# Kippstufe_astabil.net
KiCad netlist of a schematic drawn in EAGLE
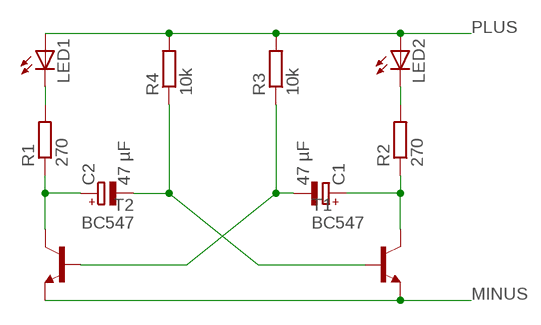
[diagram p0: schematic, sheet 1]

(export (version "E")
  (design (tool "Eeschema 10.0.6"))
  (components
    (comp (ref "C1")
      (value "47 µF")
      (footprint "eagle-import:B45181B")
      (libsource (lib "eagle-import") (part "CPOL-EUB45181B"))
    )
    (comp (ref "C2")
      (value "47 µF")
      (footprint "eagle-import:B45181B")
      (libsource (lib "eagle-import") (part "CPOL-EUB45181B"))
    )
    (comp (ref "LED1")
      (value "LED5MM")
      (footprint "eagle-import:LED5MM")
      (libsource (lib "eagle-import") (part "LED5MM"))
    )
    (comp (ref "LED2")
      (value "LED5MM")
      (footprint "eagle-import:LED5MM")
      (libsource (lib "eagle-import") (part "LED5MM"))
    )
    (comp (ref "R1")
      (value "270")
      (footprint "eagle-import:0204_7")
      (libsource (lib "eagle-import") (part "R-EU_0204/7"))
    )
    (comp (ref "R2")
      (value "270")
      (footprint "eagle-import:0204_7")
      (libsource (lib "eagle-import") (part "R-EU_0204/7"))
    )
    (comp (ref "R3")
      (value "10k")
      (footprint "eagle-import:0204_7")
      (libsource (lib "eagle-import") (part "R-EU_0204/7"))
    )
    (comp (ref "R4")
      (value "10k")
      (footprint "eagle-import:0204_7")
      (libsource (lib "eagle-import") (part "R-EU_0204/7"))
    )
    (comp (ref "T1")
      (value "BC547")
      (footprint "eagle-import:TO92")
      (libsource (lib "eagle-import") (part "BC547"))
    )
    (comp (ref "T2")
      (value "BC547")
      (footprint "eagle-import:TO92")
      (libsource (lib "eagle-import") (part "BC547"))
    )
  )
  (nets
    (net (code "1") (name "/MINUS") (class "Default")
      (node (ref "T1") (pin "1") (pinfunction "E_1") (pintype "passive"))
      (node (ref "T2") (pin "1") (pinfunction "E_1") (pintype "passive"))
    )
    (net (code "2") (name "/PLUS") (class "Default")
      (node (ref "LED1") (pin "A") (pinfunction "A_A") (pintype "passive"))
      (node (ref "LED2") (pin "A") (pinfunction "A_A") (pintype "passive"))
      (node (ref "R3") (pin "2") (pinfunction "2_2") (pintype "passive"))
      (node (ref "R4") (pin "2") (pinfunction "2_2") (pintype "passive"))
    )
    (net (code "3") (name "Net-(LED1-C)") (class "Default")
      (node (ref "LED1") (pin "K") (pinfunction "C_K") (pintype "passive"))
      (node (ref "R1") (pin "2") (pinfunction "2_2") (pintype "passive"))
    )
    (net (code "4") (name "Net-(LED2-C)") (class "Default")
      (node (ref "LED2") (pin "K") (pinfunction "C_K") (pintype "passive"))
      (node (ref "R2") (pin "2") (pinfunction "2_2") (pintype "passive"))
    )
    (net (code "5") (name "Net-(T1-B)") (class "Default")
      (node (ref "C2") (pin "-") (pinfunction "-_-") (pintype "passive"))
      (node (ref "R4") (pin "1") (pinfunction "1_1") (pintype "passive"))
      (node (ref "T1") (pin "2") (pinfunction "B_2") (pintype "passive"))
    )
    (net (code "6") (name "Net-(T1-C)") (class "Default")
      (node (ref "C1") (pin "+") (pinfunction "+_+") (pintype "passive"))
      (node (ref "R2") (pin "1") (pinfunction "1_1") (pintype "passive"))
      (node (ref "T1") (pin "3") (pinfunction "C_3") (pintype "passive"))
    )
    (net (code "7") (name "Net-(T2-B)") (class "Default")
      (node (ref "C1") (pin "-") (pinfunction "-_-") (pintype "passive"))
      (node (ref "R3") (pin "1") (pinfunction "1_1") (pintype "passive"))
      (node (ref "T2") (pin "2") (pinfunction "B_2") (pintype "passive"))
    )
    (net (code "8") (name "Net-(T2-C)") (class "Default")
      (node (ref "C2") (pin "+") (pinfunction "+_+") (pintype "passive"))
      (node (ref "R1") (pin "1") (pinfunction "1_1") (pintype "passive"))
      (node (ref "T2") (pin "3") (pinfunction "C_3") (pintype "passive"))
    )
  )
)
